# Snap4.net
KiCad netlist of a schematic drawn in Altium Designer
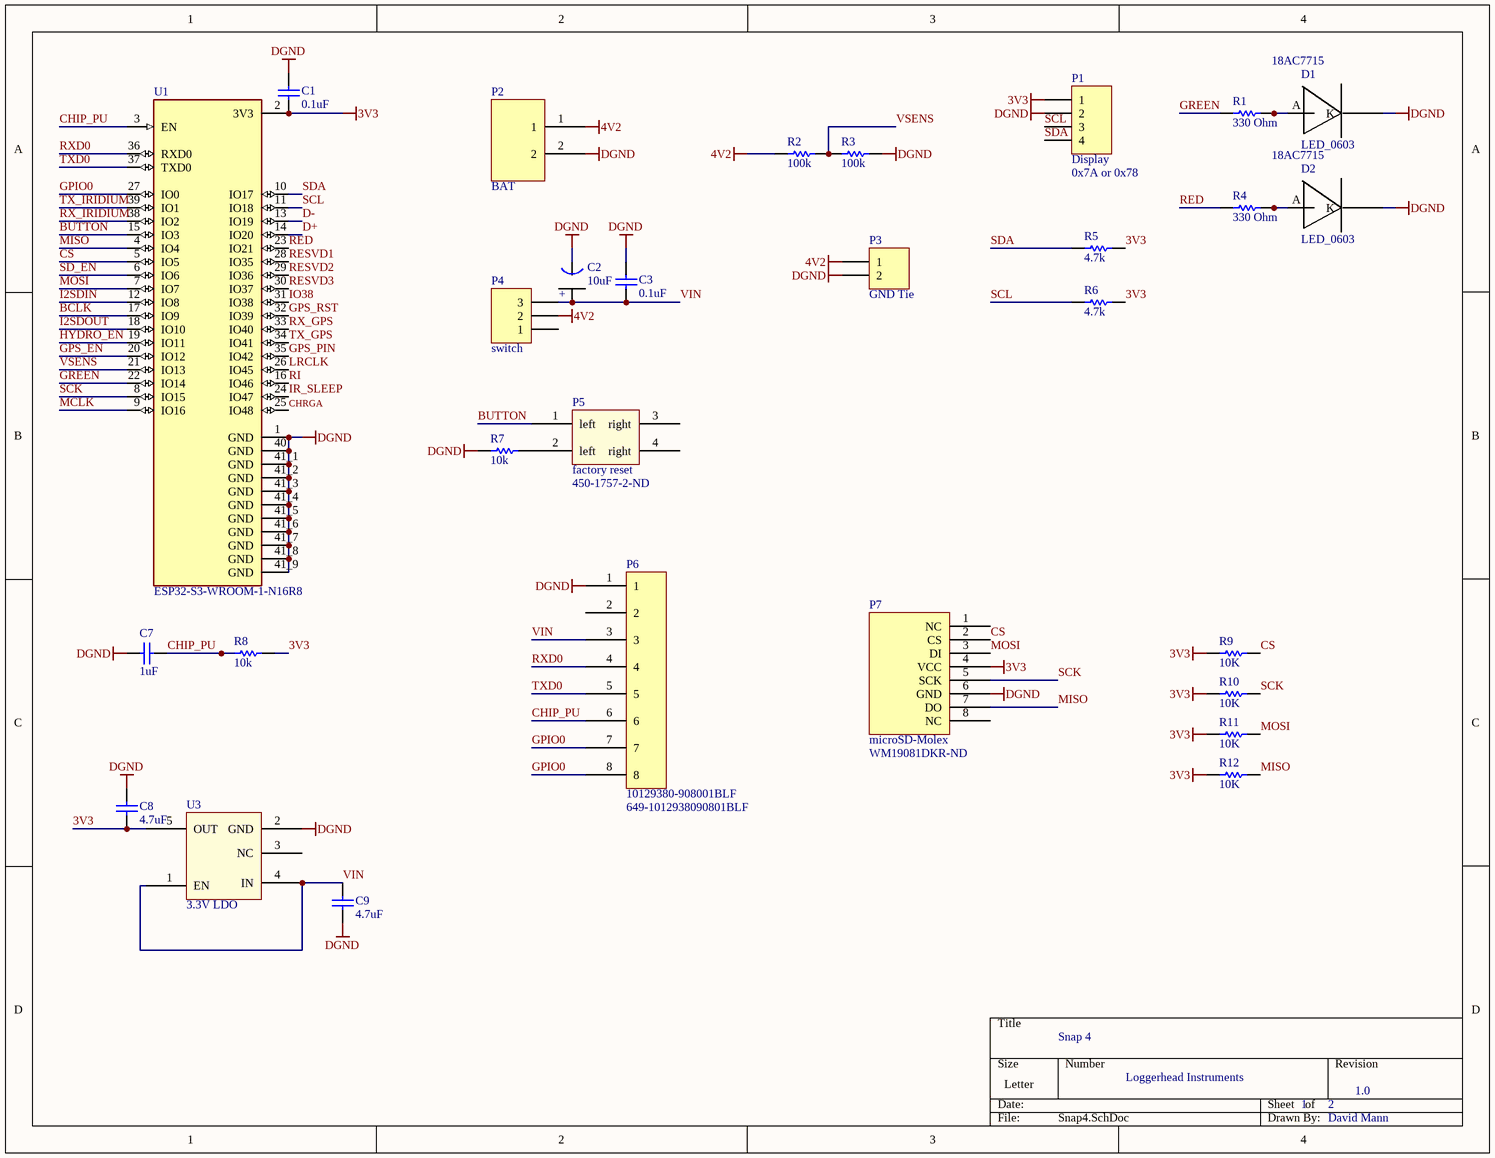
[diagram p0: Snap4.SchDoc]

(export (version "E")
  (design (tool "Eeschema 10.0.6"))
  (components
    (comp (ref "C1")
      (value "0.1uF")
      (footprint "0402")
      (description "Ceramic Chip Capacitor - Standard")
      (fields (field (name "PUBLISHER") "Altium Limited"))
      (libsource (lib "KEMET Chip Capacitor") (part "C0402"))
    )
    (comp (ref "C2") (value "10uF") (footprint "Tant0805") (libsource (lib "Loggerhead") (part "Tant0805")))
    (comp (ref "C3")
      (value "0.1uF")
      (footprint "0402")
      (description "Ceramic Chip Capacitor - Standard")
      (fields (field (name "PUBLISHER") "Altium Limited"))
      (libsource (lib "KEMET Chip Capacitor") (part "C0402"))
    )
    (comp (ref "C7")
      (value "1uF")
      (footprint "0402")
      (description "Ceramic Chip Capacitor - Standard")
      (fields (field (name "PUBLISHER") "Altium Limited"))
      (libsource (lib "KEMET Chip Capacitor") (part "C0402"))
    )
    (comp (ref "C8")
      (value "4.7uF")
      (footprint "0402")
      (description "Ceramic Chip Capacitor - Standard")
      (fields (field (name "PUBLISHER") "Altium Limited"))
      (libsource (lib "KEMET Chip Capacitor") (part "C0402"))
    )
    (comp (ref "C9")
      (value "4.7uF")
      (footprint "0402")
      (description "Ceramic Chip Capacitor - Standard")
      (fields (field (name "PUBLISHER") "Altium Limited"))
      (libsource (lib "KEMET Chip Capacitor") (part "C0402"))
    )
    (comp (ref "D1")
      (value "LED_0603")
      (footprint "Diode0603")
      (fields (field (name "SUPPLIER PART NUMBER 1") "18AC7715"))
      (libsource (lib "Loggerhead") (part "LED_0603"))
    )
    (comp (ref "D2")
      (value "LED_0603")
      (footprint "Diode0603")
      (fields (field (name "SUPPLIER PART NUMBER 1") "18AC7715"))
      (libsource (lib "Loggerhead") (part "LED_0603"))
    )
    (comp (ref "P1")
      (value "Display")
      (footprint "HDR1X4")
      (description "Header, 4-Pin")
      (fields (field (name "PUBLISHER") "Altium Limited"))
      (libsource (lib "Miscellaneous Connectors") (part "Header 4"))
    )
    (comp (ref "P2")
      (value "BAT")
      (footprint "HDR_2x1_2mm")
      (libsource (lib "Loggerhead") (part "HDR_2x1_2mm"))
    )
    (comp (ref "P3")
      (value "GND Tie")
      (footprint "HDR1X2")
      (description "Header, 2-Pin")
      (fields (field (name "PUBLISHER") "Altium Limited"))
      (libsource (lib "Miscellaneous Connectors") (part "Header 2"))
    )
    (comp (ref "P4")
      (value "switch")
      (footprint "HDR1X3")
      (description "Header, 3-Pin")
      (fields (field (name "PUBLISHER") "Altium Limited"))
      (libsource (lib "Miscellaneous Connectors") (part "Header 3"))
    )
    (comp (ref "P5")
      (value "factory reset")
      (footprint "SOP4")
      (fields (field (name "SUPPLIER PART NUMBER 1") "450-1757-2-ND"))
      (libsource (lib "Loggerhead") (part "pushbutton"))
    )
    (comp (ref "P6")
      (value "10129380-908001BLF")
      (footprint "Header_8_SMT")
      (description "Surface mount header")
      (fields (field (name "SUPPLIER PART NUMBER 1") "649-1012938090801BLF"))
      (libsource (lib "Loggerhead") (part "Header8_SMT"))
    )
    (comp (ref "P7")
      (value "microSD-Molex")
      (footprint "microSD_Molex_hinged")
      (fields (field (name "SUPPLIER PART NUMBER 1") "WM19081DKR-ND"))
      (libsource (lib "Loggerhead") (part "microSD_Molex_hinged"))
    )
    (comp (ref "R1")
      (value "330 Ohm")
      (footprint "2-0402")
      (fields (field (name "PUBLISHER") "Altium Limited"))
      (libsource (lib "Panasonic Resistor") (part "ERJ2RB"))
    )
    (comp (ref "R2")
      (value "100k")
      (footprint "3-0603")
      (fields (field (name "PUBLISHER") "Altium Limited"))
      (libsource (lib "Panasonic Resistor") (part "ERJ3RK"))
    )
    (comp (ref "R3")
      (value "100k")
      (footprint "3-0603")
      (fields (field (name "PUBLISHER") "Altium Limited"))
      (libsource (lib "Panasonic Resistor") (part "ERJ3RK"))
    )
    (comp (ref "R4")
      (value "330 Ohm")
      (footprint "2-0402")
      (fields (field (name "PUBLISHER") "Altium Limited"))
      (libsource (lib "Panasonic Resistor") (part "ERJ2RB"))
    )
    (comp (ref "R5")
      (value "4.7k")
      (footprint "3-0603")
      (fields (field (name "PUBLISHER") "Altium Limited"))
      (libsource (lib "Panasonic Resistor") (part "ERJ3RK"))
    )
    (comp (ref "R6")
      (value "4.7k")
      (footprint "3-0603")
      (fields (field (name "PUBLISHER") "Altium Limited"))
      (libsource (lib "Panasonic Resistor") (part "ERJ3RK"))
    )
    (comp (ref "R7")
      (value "10k")
      (footprint "2-0402")
      (fields (field (name "PUBLISHER") "Altium Limited"))
      (libsource (lib "Panasonic Resistor") (part "ERJ2RB"))
    )
    (comp (ref "R8")
      (value "10k")
      (footprint "2-0402")
      (fields (field (name "PUBLISHER") "Altium Limited"))
      (libsource (lib "Panasonic Resistor") (part "ERJ2RB"))
    )
    (comp (ref "R9")
      (value "10K")
      (footprint "3-0603")
      (fields (field (name "PUBLISHER") "Altium Limited"))
      (libsource (lib "Panasonic Resistor") (part "ERJ3EK"))
    )
    (comp (ref "R10")
      (value "10K")
      (footprint "3-0603")
      (fields (field (name "PUBLISHER") "Altium Limited"))
      (libsource (lib "Panasonic Resistor") (part "ERJ3EK"))
    )
    (comp (ref "R11")
      (value "10K")
      (footprint "3-0603")
      (fields (field (name "PUBLISHER") "Altium Limited"))
      (libsource (lib "Panasonic Resistor") (part "ERJ3EK"))
    )
    (comp (ref "R12")
      (value "10K")
      (footprint "3-0603")
      (fields (field (name "PUBLISHER") "Altium Limited"))
      (libsource (lib "Panasonic Resistor") (part "ERJ3EK"))
    )
    (comp (ref "U1")
      (value "ESP32-S3-WROOM-1-N16R8")
      (footprint "XCVR_ESP32-S3-WROOM-1-N16R2")
      (description "Bluetooth, WiFi 802.11b/g/n, Bluetooth v5.0 Transceiver Module 2.4GHz PCB Trace Surface Mount")
      (fields (field (name "MP") "ESP32-S3-WROOM-1-N16R2") (field (name "MF") "Espressif Systems"))
      (libsource (lib "ESP32-S3-WROOM-1-N16R2") (part "ESP32-S3-WROOM-1-N16R2"))
    )
    (comp (ref "U3")
      (value "3.3V LDO")
      (footprint "AP7361C-33Y5-13")
      (libsource (lib "Loggerhead") (part "AP7361C-33Y5-13"))
    )
  )
  (nets
    (net (code "1") (name "/BCLK") (class "Default")
      (node (ref "U1") (pin "17") (pinfunction "IO9_17") (pintype "bidirectional"))
    )
    (net (code "2") (name "/BUTTON") (class "Default")
      (node (ref "P5") (pin "1") (pinfunction "left_1") (pintype "passive"))
      (node (ref "U1") (pin "15") (pinfunction "IO3_15") (pintype "bidirectional"))
    )
    (net (code "3") (name "/CHIP_PU") (class "Default")
      (node (ref "C7") (pin "1") (pinfunction "1_1") (pintype "passive"))
      (node (ref "P6") (pin "6") (pinfunction "6_6") (pintype "passive"))
      (node (ref "R8") (pin "2") (pinfunction "2_2") (pintype "passive"))
      (node (ref "U1") (pin "3") (pinfunction "EN_3") (pintype "input"))
    )
    (net (code "4") (name "/CHRGA") (class "Default")
      (node (ref "U1") (pin "25") (pinfunction "IO48_25") (pintype "bidirectional"))
    )
    (net (code "5") (name "/CS") (class "Default")
      (node (ref "P7") (pin "2") (pinfunction "CS_2") (pintype "passive"))
      (node (ref "R9") (pin "2") (pinfunction "2_2") (pintype "passive"))
      (node (ref "U1") (pin "5") (pinfunction "IO5_5") (pintype "bidirectional"))
    )
    (net (code "6") (name "/D+") (class "Default")
      (node (ref "U1") (pin "14") (pinfunction "IO20_14") (pintype "bidirectional"))
    )
    (net (code "7") (name "/D-") (class "Default")
      (node (ref "U1") (pin "13") (pinfunction "IO19_13") (pintype "bidirectional"))
    )
    (net (code "8") (name "/GPIO0") (class "Default")
      (node (ref "P6") (pin "7") (pinfunction "7_7") (pintype "passive"))
      (node (ref "P6") (pin "8") (pinfunction "8_8") (pintype "passive"))
      (node (ref "U1") (pin "27") (pinfunction "IO0_27") (pintype "bidirectional"))
    )
    (net (code "9") (name "/GPS_EN") (class "Default")
      (node (ref "U1") (pin "20") (pinfunction "IO12_20") (pintype "bidirectional"))
    )
    (net (code "10") (name "/GPS_PIN") (class "Default")
      (node (ref "U1") (pin "35") (pinfunction "IO42_35") (pintype "bidirectional"))
    )
    (net (code "11") (name "/GPS_RST") (class "Default")
      (node (ref "U1") (pin "32") (pinfunction "IO39_32") (pintype "bidirectional"))
    )
    (net (code "12") (name "/GREEN") (class "Default")
      (node (ref "R1") (pin "2") (pinfunction "2_2") (pintype "passive"))
      (node (ref "U1") (pin "22") (pinfunction "IO14_22") (pintype "bidirectional"))
    )
    (net (code "13") (name "/HYDRO_EN") (class "Default")
      (node (ref "U1") (pin "19") (pinfunction "IO11_19") (pintype "bidirectional"))
    )
    (net (code "14") (name "/I2SDIN") (class "Default")
      (node (ref "U1") (pin "12") (pinfunction "IO8_12") (pintype "bidirectional"))
    )
    (net (code "15") (name "/I2SDOUT") (class "Default")
      (node (ref "U1") (pin "18") (pinfunction "IO10_18") (pintype "bidirectional"))
    )
    (net (code "16") (name "/IO38") (class "Default")
      (node (ref "U1") (pin "31") (pinfunction "IO38_31") (pintype "bidirectional"))
    )
    (net (code "17") (name "/IR_SLEEP") (class "Default")
      (node (ref "U1") (pin "24") (pinfunction "IO47_24") (pintype "bidirectional"))
    )
    (net (code "18") (name "/LRCLK") (class "Default")
      (node (ref "U1") (pin "26") (pinfunction "IO45_26") (pintype "bidirectional"))
    )
    (net (code "19") (name "/MCLK") (class "Default")
      (node (ref "U1") (pin "9") (pinfunction "IO16_9") (pintype "bidirectional"))
    )
    (net (code "20") (name "/MISO") (class "Default")
      (node (ref "P7") (pin "7") (pinfunction "DO_7") (pintype "passive"))
      (node (ref "R12") (pin "2") (pinfunction "2_2") (pintype "passive"))
      (node (ref "U1") (pin "4") (pinfunction "IO4_4") (pintype "bidirectional"))
    )
    (net (code "21") (name "/MOSI") (class "Default")
      (node (ref "P7") (pin "3") (pinfunction "DI_3") (pintype "passive"))
      (node (ref "R11") (pin "2") (pinfunction "2_2") (pintype "passive"))
      (node (ref "U1") (pin "7") (pinfunction "IO7_7") (pintype "bidirectional"))
    )
    (net (code "22") (name "/RED") (class "Default")
      (node (ref "R4") (pin "2") (pinfunction "2_2") (pintype "passive"))
      (node (ref "U1") (pin "23") (pinfunction "IO21_23") (pintype "bidirectional"))
    )
    (net (code "23") (name "/RESVD1") (class "Default")
      (node (ref "U1") (pin "28") (pinfunction "IO35_28") (pintype "bidirectional"))
    )
    (net (code "24") (name "/RESVD2") (class "Default")
      (node (ref "U1") (pin "29") (pinfunction "IO36_29") (pintype "bidirectional"))
    )
    (net (code "25") (name "/RESVD3") (class "Default")
      (node (ref "U1") (pin "30") (pinfunction "IO37_30") (pintype "bidirectional"))
    )
    (net (code "26") (name "/RI") (class "Default")
      (node (ref "U1") (pin "16") (pinfunction "IO46_16") (pintype "bidirectional"))
    )
    (net (code "27") (name "/RXD0") (class "Default")
      (node (ref "P6") (pin "4") (pinfunction "4_4") (pintype "passive"))
      (node (ref "U1") (pin "36") (pinfunction "RXD0_36") (pintype "bidirectional"))
    )
    (net (code "28") (name "/RX_GPS") (class "Default")
      (node (ref "U1") (pin "33") (pinfunction "IO40_33") (pintype "bidirectional"))
    )
    (net (code "29") (name "/RX_IRIDIUM") (class "Default")
      (node (ref "U1") (pin "38") (pinfunction "IO2_38") (pintype "bidirectional"))
    )
    (net (code "30") (name "/SCK") (class "Default")
      (node (ref "P7") (pin "5") (pinfunction "SCK_5") (pintype "passive"))
      (node (ref "R10") (pin "2") (pinfunction "2_2") (pintype "passive"))
      (node (ref "U1") (pin "8") (pinfunction "IO15_8") (pintype "bidirectional"))
    )
    (net (code "31") (name "/SCL") (class "Default")
      (node (ref "P1") (pin "3") (pinfunction "3_3") (pintype "passive"))
      (node (ref "R6") (pin "1") (pinfunction "1_1") (pintype "passive"))
      (node (ref "U1") (pin "11") (pinfunction "IO18_11") (pintype "bidirectional"))
    )
    (net (code "32") (name "/SDA") (class "Default")
      (node (ref "P1") (pin "4") (pinfunction "4_4") (pintype "passive"))
      (node (ref "R5") (pin "1") (pinfunction "1_1") (pintype "passive"))
      (node (ref "U1") (pin "10") (pinfunction "IO17_10") (pintype "bidirectional"))
    )
    (net (code "33") (name "/SD_EN") (class "Default")
      (node (ref "U1") (pin "6") (pinfunction "IO6_6") (pintype "bidirectional"))
    )
    (net (code "34") (name "/TXD0") (class "Default")
      (node (ref "P6") (pin "5") (pinfunction "5_5") (pintype "passive"))
      (node (ref "U1") (pin "37") (pinfunction "TXD0_37") (pintype "bidirectional"))
    )
    (net (code "35") (name "/TX_GPS") (class "Default")
      (node (ref "U1") (pin "34") (pinfunction "IO41_34") (pintype "bidirectional"))
    )
    (net (code "36") (name "/TX_IRIDIUM") (class "Default")
      (node (ref "U1") (pin "39") (pinfunction "IO1_39") (pintype "bidirectional"))
    )
    (net (code "37") (name "/VIN") (class "Default")
      (node (ref "C2") (pin "2") (pinfunction "+_2") (pintype "passive"))
      (node (ref "C3") (pin "1") (pinfunction "1_1") (pintype "passive"))
      (node (ref "C9") (pin "1") (pinfunction "1_1") (pintype "passive"))
      (node (ref "P4") (pin "3") (pinfunction "3_3") (pintype "passive"))
      (node (ref "P6") (pin "3") (pinfunction "3_3") (pintype "passive"))
      (node (ref "U3") (pin "1") (pinfunction "EN_1") (pintype "passive"))
      (node (ref "U3") (pin "4") (pinfunction "IN_4") (pintype "passive"))
    )
    (net (code "38") (name "/VSENS") (class "Default")
      (node (ref "R2") (pin "1") (pinfunction "1_1") (pintype "passive"))
      (node (ref "R3") (pin "2") (pinfunction "2_2") (pintype "passive"))
      (node (ref "U1") (pin "21") (pinfunction "IO13_21") (pintype "bidirectional"))
    )
    (net (code "39") (name "3V3") (class "Default")
      (node (ref "C1") (pin "1") (pinfunction "1_1") (pintype "passive"))
      (node (ref "C8") (pin "2") (pinfunction "2_2") (pintype "passive"))
      (node (ref "P1") (pin "1") (pinfunction "1_1") (pintype "passive"))
      (node (ref "P7") (pin "4") (pinfunction "VCC_4") (pintype "passive"))
      (node (ref "R10") (pin "1") (pinfunction "1_1") (pintype "passive"))
      (node (ref "R11") (pin "1") (pinfunction "1_1") (pintype "passive"))
      (node (ref "R12") (pin "1") (pinfunction "1_1") (pintype "passive"))
      (node (ref "R5") (pin "2") (pinfunction "2_2") (pintype "passive"))
      (node (ref "R6") (pin "2") (pinfunction "2_2") (pintype "passive"))
      (node (ref "R8") (pin "1") (pinfunction "1_1") (pintype "passive"))
      (node (ref "R9") (pin "1") (pinfunction "1_1") (pintype "passive"))
      (node (ref "U1") (pin "2") (pinfunction "3V3_2") (pintype "power_in"))
      (node (ref "U3") (pin "5") (pinfunction "OUT_5") (pintype "passive"))
    )
    (net (code "40") (name "4V2") (class "Default")
      (node (ref "P2") (pin "1") (pinfunction "1_1") (pintype "passive"))
      (node (ref "P3") (pin "1") (pinfunction "1_1") (pintype "passive"))
      (node (ref "P4") (pin "2") (pinfunction "2_2") (pintype "passive"))
      (node (ref "R2") (pin "2") (pinfunction "2_2") (pintype "passive"))
    )
    (net (code "41") (name "DGND") (class "Default")
      (node (ref "C1") (pin "2") (pinfunction "2_2") (pintype "passive"))
      (node (ref "C2") (pin "1") (pinfunction "GND_1") (pintype "passive"))
      (node (ref "C3") (pin "2") (pinfunction "2_2") (pintype "passive"))
      (node (ref "C7") (pin "2") (pinfunction "2_2") (pintype "passive"))
      (node (ref "C8") (pin "1") (pinfunction "1_1") (pintype "passive"))
      (node (ref "C9") (pin "2") (pinfunction "2_2") (pintype "passive"))
      (node (ref "D1") (pin "K") (pinfunction "K_K") (pintype "passive"))
      (node (ref "D2") (pin "K") (pinfunction "K_K") (pintype "passive"))
      (node (ref "P1") (pin "2") (pinfunction "2_2") (pintype "passive"))
      (node (ref "P2") (pin "2") (pinfunction "2_2") (pintype "passive"))
      (node (ref "P3") (pin "2") (pinfunction "2_2") (pintype "passive"))
      (node (ref "P6") (pin "1") (pinfunction "1_1") (pintype "passive"))
      (node (ref "P7") (pin "6") (pinfunction "GND_6") (pintype "passive"))
      (node (ref "R3") (pin "1") (pinfunction "1_1") (pintype "passive"))
      (node (ref "R7") (pin "2") (pinfunction "2_2") (pintype "passive"))
      (node (ref "U1") (pin "1") (pinfunction "GND_1") (pintype "power_in"))
      (node (ref "U1") (pin "40") (pinfunction "GND_40") (pintype "power_in"))
      (node (ref "U1") (pin "41_1") (pinfunction "GND_41_1") (pintype "power_in"))
      (node (ref "U1") (pin "41_2") (pinfunction "GND_41_2") (pintype "power_in"))
      (node (ref "U1") (pin "41_3") (pinfunction "GND_41_3") (pintype "power_in"))
      (node (ref "U1") (pin "41_4") (pinfunction "GND_41_4") (pintype "power_in"))
      (node (ref "U1") (pin "41_5") (pinfunction "GND_41_5") (pintype "power_in"))
      (node (ref "U1") (pin "41_6") (pinfunction "GND_41_6") (pintype "power_in"))
      (node (ref "U1") (pin "41_7") (pinfunction "GND_41_7") (pintype "power_in"))
      (node (ref "U1") (pin "41_8") (pinfunction "GND_41_8") (pintype "power_in"))
      (node (ref "U1") (pin "41_9") (pinfunction "GND_41_9") (pintype "power_in"))
      (node (ref "U3") (pin "2") (pinfunction "GND_2") (pintype "passive"))
    )
    (net (code "42") (name "Net-(D1-PadA)") (class "Default")
      (node (ref "D1") (pin "A") (pinfunction "A_A") (pintype "passive"))
      (node (ref "R1") (pin "1") (pinfunction "1_1") (pintype "passive"))
    )
    (net (code "43") (name "Net-(D2-PadA)") (class "Default")
      (node (ref "D2") (pin "A") (pinfunction "A_A") (pintype "passive"))
      (node (ref "R4") (pin "1") (pinfunction "1_1") (pintype "passive"))
    )
    (net (code "44") (name "Net-(P5-left-Pad2)") (class "Default")
      (node (ref "P5") (pin "2") (pinfunction "left_2") (pintype "passive"))
      (node (ref "R7") (pin "1") (pinfunction "1_1") (pintype "passive"))
    )
    (net (code "45") (name "unconnected-(P4-Pad1)") (class "Default")
      (node (ref "P4") (pin "1") (pinfunction "1_1") (pintype "passive"))
    )
    (net (code "46") (name "unconnected-(P5-right-Pad3)") (class "Default")
      (node (ref "P5") (pin "3") (pinfunction "right_3") (pintype "passive"))
    )
    (net (code "47") (name "unconnected-(P5-right-Pad4)") (class "Default")
      (node (ref "P5") (pin "4") (pinfunction "right_4") (pintype "passive"))
    )
    (net (code "48") (name "unconnected-(P6-Pad2)") (class "Default")
      (node (ref "P6") (pin "2") (pinfunction "2_2") (pintype "passive"))
    )
    (net (code "49") (name "unconnected-(P7-NC-Pad1)") (class "Default")
      (node (ref "P7") (pin "1") (pinfunction "NC_1") (pintype "passive"))
    )
    (net (code "50") (name "unconnected-(P7-NC-Pad8)") (class "Default")
      (node (ref "P7") (pin "8") (pinfunction "NC_8") (pintype "passive"))
    )
    (net (code "51") (name "unconnected-(U3-NC-Pad3)") (class "Default")
      (node (ref "U3") (pin "3") (pinfunction "NC_3") (pintype "passive"))
    )
  )
)
